# Driver.net
KiCad netlist of a schematic drawn in EAGLE
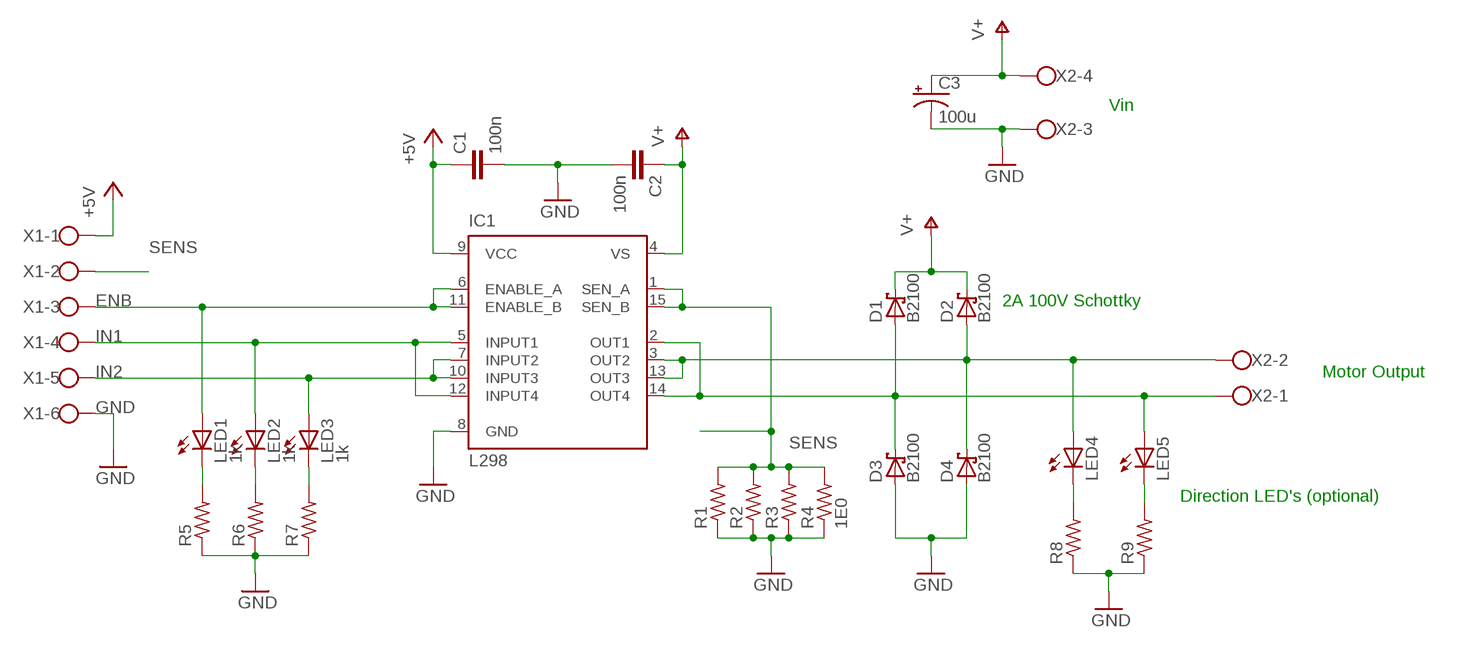
[diagram p0: schematic, sheet 1]

(export (version "E")
  (design (tool "Eeschema 10.0.6"))
  (components
    (comp (ref "C1")
      (value "100n")
      (footprint "eagle-import:C0805K")
      (libsource (lib "eagle-import") (part "C-EUC0805K"))
    )
    (comp (ref "C2")
      (value "100n")
      (footprint "eagle-import:C0805K")
      (libsource (lib "eagle-import") (part "C-EUC0805K"))
    )
    (comp (ref "C3")
      (value "100u")
      (footprint "eagle-import:E7,5-16")
      (libsource (lib "eagle-import") (part "CPOL-USE7.5-16"))
    )
    (comp (ref "D1")
      (value "B2100")
      (footprint "eagle-import:SMC")
      (libsource (lib "eagle-import") (part "MBRS30T34"))
    )
    (comp (ref "D2")
      (value "B2100")
      (footprint "eagle-import:SMC")
      (libsource (lib "eagle-import") (part "MBRS30T34"))
    )
    (comp (ref "D3")
      (value "B2100")
      (footprint "eagle-import:SMC")
      (libsource (lib "eagle-import") (part "MBRS30T34"))
    )
    (comp (ref "D4")
      (value "B2100")
      (footprint "eagle-import:SMC")
      (libsource (lib "eagle-import") (part "MBRS30T34"))
    )
    (comp (ref "IC1")
      (value "L298")
      (footprint "eagle-import:MULTIWATT-15")
      (fields (field (name "MPN") "L298N"))
      (libsource (lib "eagle-import") (part "L298"))
    )
    (comp (ref "LED1")
      (value "1k")
      (footprint "eagle-import:LED3MM")
      (libsource (lib "eagle-import") (part "LED3MM"))
    )
    (comp (ref "LED2")
      (value "1k")
      (footprint "eagle-import:LED3MM")
      (libsource (lib "eagle-import") (part "LED3MM"))
    )
    (comp (ref "LED3")
      (value "1k")
      (footprint "eagle-import:LED3MM")
      (libsource (lib "eagle-import") (part "LED3MM"))
    )
    (comp (ref "LED4")
      (value "LED3MM")
      (footprint "eagle-import:LED3MM")
      (libsource (lib "eagle-import") (part "LED3MM"))
    )
    (comp (ref "LED5")
      (value "LED3MM")
      (footprint "eagle-import:LED3MM")
      (libsource (lib "eagle-import") (part "LED3MM"))
    )
    (comp (ref "R1")
      (value "R-US_R2512")
      (footprint "eagle-import:R2512")
      (libsource (lib "eagle-import") (part "R-US_R2512"))
    )
    (comp (ref "R2")
      (value "R-US_R2512")
      (footprint "eagle-import:R2512")
      (libsource (lib "eagle-import") (part "R-US_R2512"))
    )
    (comp (ref "R3")
      (value "R-US_R2512")
      (footprint "eagle-import:R2512")
      (libsource (lib "eagle-import") (part "R-US_R2512"))
    )
    (comp (ref "R4")
      (value "1E0")
      (footprint "eagle-import:R2512")
      (libsource (lib "eagle-import") (part "R-US_R2512"))
    )
    (comp (ref "R5")
      (value "R-US_R0805")
      (footprint "eagle-import:R0805")
      (libsource (lib "eagle-import") (part "R-US_R0805"))
    )
    (comp (ref "R6")
      (value "R-US_R0805")
      (footprint "eagle-import:R0805")
      (libsource (lib "eagle-import") (part "R-US_R0805"))
    )
    (comp (ref "R7")
      (value "R-US_R0805")
      (footprint "eagle-import:R0805")
      (libsource (lib "eagle-import") (part "R-US_R0805"))
    )
    (comp (ref "R8")
      (value "R-US_R0805")
      (footprint "eagle-import:R0805")
      (libsource (lib "eagle-import") (part "R-US_R0805"))
    )
    (comp (ref "R9")
      (value "R-US_R0805")
      (footprint "eagle-import:R0805")
      (libsource (lib "eagle-import") (part "R-US_R0805"))
    )
    (comp (ref "X1")
      (value "W237-6")
      (footprint "eagle-import:W237-6")
      (libsource (lib "eagle-import") (part "W237-6"))
    )
    (comp (ref "X2")
      (value "W237-4")
      (footprint "eagle-import:W237-4")
      (libsource (lib "eagle-import") (part "W237-4"))
    )
  )
  (nets
    (net (code "1") (name "+5V") (class "Default")
      (node (ref "C1") (pin "1") (pinfunction "1_1") (pintype "passive"))
      (node (ref "IC1") (pin "9") (pinfunction "VCC_9") (pintype "power_in"))
      (node (ref "X1") (pin "1") (pinfunction "KL_1") (pintype "passive"))
    )
    (net (code "2") (name "/ENB") (class "Default")
      (node (ref "IC1") (pin "11") (pinfunction "ENABLE_B_11") (pintype "input"))
      (node (ref "IC1") (pin "6") (pinfunction "ENABLE_A_6") (pintype "input"))
      (node (ref "LED1") (pin "A") (pinfunction "A_A") (pintype "passive"))
      (node (ref "X1") (pin "3") (pinfunction "KL_3") (pintype "passive"))
    )
    (net (code "3") (name "/IN1") (class "Default")
      (node (ref "IC1") (pin "12") (pinfunction "INPUT4_12") (pintype "input"))
      (node (ref "IC1") (pin "5") (pinfunction "INPUT1_5") (pintype "input"))
      (node (ref "LED2") (pin "A") (pinfunction "A_A") (pintype "passive"))
      (node (ref "X1") (pin "4") (pinfunction "KL_4") (pintype "passive"))
    )
    (net (code "4") (name "/IN2") (class "Default")
      (node (ref "IC1") (pin "10") (pinfunction "INPUT3_10") (pintype "input"))
      (node (ref "IC1") (pin "7") (pinfunction "INPUT2_7") (pintype "input"))
      (node (ref "LED3") (pin "A") (pinfunction "A_A") (pintype "passive"))
      (node (ref "X1") (pin "5") (pinfunction "KL_5") (pintype "passive"))
    )
    (net (code "5") (name "/SENS") (class "Default")
      (node (ref "IC1") (pin "1") (pinfunction "SEN_A_1") (pintype "input"))
      (node (ref "IC1") (pin "15") (pinfunction "SEN_B_15") (pintype "input"))
      (node (ref "R1") (pin "2") (pinfunction "2_2") (pintype "passive"))
      (node (ref "R2") (pin "2") (pinfunction "2_2") (pintype "passive"))
      (node (ref "R3") (pin "2") (pinfunction "2_2") (pintype "passive"))
      (node (ref "R4") (pin "2") (pinfunction "2_2") (pintype "passive"))
      (node (ref "X1") (pin "2") (pinfunction "KL_2") (pintype "passive"))
    )
    (net (code "6") (name "GND") (class "Default")
      (node (ref "C1") (pin "2") (pinfunction "2_2") (pintype "passive"))
      (node (ref "C2") (pin "2") (pinfunction "2_2") (pintype "passive"))
      (node (ref "C3") (pin "-") (pinfunction "-_-") (pintype "passive"))
      (node (ref "D3") (pin "A") (pinfunction "A_A") (pintype "passive"))
      (node (ref "D4") (pin "A") (pinfunction "A_A") (pintype "passive"))
      (node (ref "IC1") (pin "8") (pinfunction "GND_8") (pintype "power_in"))
      (node (ref "R1") (pin "1") (pinfunction "1_1") (pintype "passive"))
      (node (ref "R2") (pin "1") (pinfunction "1_1") (pintype "passive"))
      (node (ref "R3") (pin "1") (pinfunction "1_1") (pintype "passive"))
      (node (ref "R4") (pin "1") (pinfunction "1_1") (pintype "passive"))
      (node (ref "R5") (pin "1") (pinfunction "1_1") (pintype "passive"))
      (node (ref "R6") (pin "1") (pinfunction "1_1") (pintype "passive"))
      (node (ref "R7") (pin "1") (pinfunction "1_1") (pintype "passive"))
      (node (ref "R8") (pin "1") (pinfunction "1_1") (pintype "passive"))
      (node (ref "R9") (pin "1") (pinfunction "1_1") (pintype "passive"))
      (node (ref "X1") (pin "6") (pinfunction "KL_6") (pintype "passive"))
      (node (ref "X2") (pin "3") (pinfunction "KL_3") (pintype "passive"))
    )
    (net (code "7") (name "Net-(IC1-OUT1)") (class "Default")
      (node (ref "D1") (pin "A") (pinfunction "A_A") (pintype "passive"))
      (node (ref "D3") (pin "C") (pinfunction "C_C") (pintype "passive"))
      (node (ref "IC1") (pin "14") (pinfunction "OUT4_14") (pintype "output"))
      (node (ref "IC1") (pin "2") (pinfunction "OUT1_2") (pintype "output"))
      (node (ref "LED5") (pin "A") (pinfunction "A_A") (pintype "passive"))
      (node (ref "X2") (pin "1") (pinfunction "KL_1") (pintype "passive"))
    )
    (net (code "8") (name "Net-(IC1-OUT2)") (class "Default")
      (node (ref "D2") (pin "A") (pinfunction "A_A") (pintype "passive"))
      (node (ref "D4") (pin "C") (pinfunction "C_C") (pintype "passive"))
      (node (ref "IC1") (pin "13") (pinfunction "OUT3_13") (pintype "output"))
      (node (ref "IC1") (pin "3") (pinfunction "OUT2_3") (pintype "output"))
      (node (ref "LED4") (pin "A") (pinfunction "A_A") (pintype "passive"))
      (node (ref "X2") (pin "2") (pinfunction "KL_2") (pintype "passive"))
    )
    (net (code "9") (name "Net-(LED1-C)") (class "Default")
      (node (ref "LED1") (pin "K") (pinfunction "C_K") (pintype "passive"))
      (node (ref "R5") (pin "2") (pinfunction "2_2") (pintype "passive"))
    )
    (net (code "10") (name "Net-(LED2-C)") (class "Default")
      (node (ref "LED2") (pin "K") (pinfunction "C_K") (pintype "passive"))
      (node (ref "R6") (pin "2") (pinfunction "2_2") (pintype "passive"))
    )
    (net (code "11") (name "Net-(LED3-C)") (class "Default")
      (node (ref "LED3") (pin "K") (pinfunction "C_K") (pintype "passive"))
      (node (ref "R7") (pin "2") (pinfunction "2_2") (pintype "passive"))
    )
    (net (code "12") (name "Net-(LED4-C)") (class "Default")
      (node (ref "LED4") (pin "K") (pinfunction "C_K") (pintype "passive"))
      (node (ref "R8") (pin "2") (pinfunction "2_2") (pintype "passive"))
    )
    (net (code "13") (name "Net-(LED5-C)") (class "Default")
      (node (ref "LED5") (pin "K") (pinfunction "C_K") (pintype "passive"))
      (node (ref "R9") (pin "2") (pinfunction "2_2") (pintype "passive"))
    )
    (net (code "14") (name "V+") (class "Default")
      (node (ref "C2") (pin "1") (pinfunction "1_1") (pintype "passive"))
      (node (ref "C3") (pin "+") (pinfunction "+_+") (pintype "passive"))
      (node (ref "D1") (pin "C") (pinfunction "C_C") (pintype "passive"))
      (node (ref "D2") (pin "C") (pinfunction "C_C") (pintype "passive"))
      (node (ref "IC1") (pin "4") (pinfunction "VS_4") (pintype "power_in"))
      (node (ref "X2") (pin "4") (pinfunction "KL_4") (pintype "passive"))
    )
  )
)
